# RFDuino_breakout.net
KiCad netlist of a schematic drawn in EAGLE
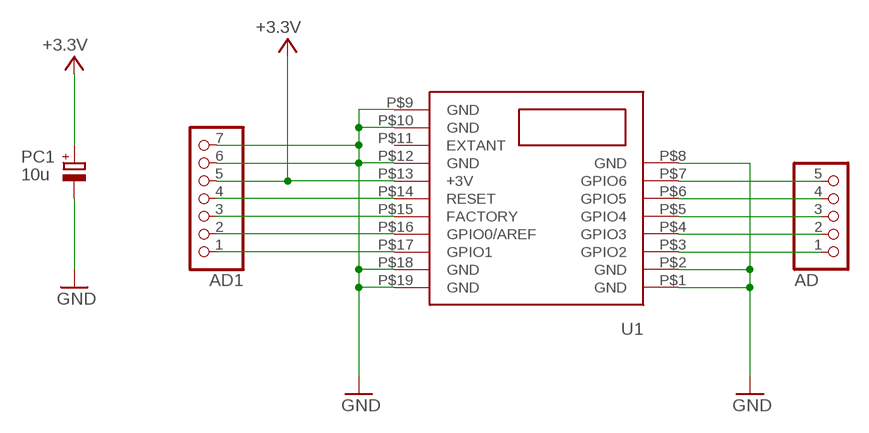
[diagram p0: schematic, sheet 1]

(export (version "E")
  (design (tool "Eeschema 10.0.6"))
  (components
    (comp (ref "AD")
      (value "PINHD-1X5")
      (footprint "eagle-import:1X05")
      (libsource (lib "eagle-import") (part "PINHD-1X5"))
    )
    (comp (ref "AD1")
      (value "PINHD-1X7")
      (footprint "eagle-import:1X07")
      (libsource (lib "eagle-import") (part "PINHD-1X7"))
    )
    (comp (ref "PC1")
      (value "10u")
      (footprint "eagle-import:PANASONIC_D")
      (libsource (lib "eagle-import") (part "CPOL-EUD"))
    )
    (comp (ref "U1")
      (value "RFD22301")
      (footprint "eagle-import:RFD22301")
      (libsource (lib "eagle-import") (part "RFD22301"))
    )
  )
  (nets
    (net (code "1") (name "+3.3V") (class "Default")
      (node (ref "AD1") (pin "5") (pinfunction "5_5") (pintype "passive"))
      (node (ref "PC1") (pin "+") (pinfunction "+_+") (pintype "passive"))
      (node (ref "U1") (pin "P$13") (pinfunction "+3V_P$13") (pintype "bidirectional"))
    )
    (net (code "2") (name "GND") (class "Default")
      (node (ref "AD1") (pin "6") (pinfunction "6_6") (pintype "passive"))
      (node (ref "AD1") (pin "7") (pinfunction "7_7") (pintype "passive"))
      (node (ref "PC1") (pin "-") (pinfunction "-_-") (pintype "passive"))
      (node (ref "U1") (pin "P$1") (pinfunction "GND_P$1") (pintype "bidirectional"))
      (node (ref "U1") (pin "P$10") (pinfunction "GND_P$10") (pintype "bidirectional"))
      (node (ref "U1") (pin "P$12") (pinfunction "GND_P$12") (pintype "bidirectional"))
      (node (ref "U1") (pin "P$18") (pinfunction "GND_P$18") (pintype "bidirectional"))
      (node (ref "U1") (pin "P$19") (pinfunction "GND_P$19") (pintype "bidirectional"))
      (node (ref "U1") (pin "P$2") (pinfunction "GND_P$2") (pintype "bidirectional"))
      (node (ref "U1") (pin "P$8") (pinfunction "GND_P$8") (pintype "bidirectional"))
      (node (ref "U1") (pin "P$9") (pinfunction "GND_P$9") (pintype "bidirectional"))
    )
    (net (code "3") (name "Net-(U1-FACTORY)") (class "Default")
      (node (ref "AD1") (pin "3") (pinfunction "3_3") (pintype "passive"))
      (node (ref "U1") (pin "P$15") (pinfunction "FACTORY_P$15") (pintype "bidirectional"))
    )
    (net (code "4") (name "Net-(U1-GPIO0{slash}AREF)") (class "Default")
      (node (ref "AD1") (pin "2") (pinfunction "2_2") (pintype "passive"))
      (node (ref "U1") (pin "P$16") (pinfunction "GPIO0/AREF_P$16") (pintype "bidirectional"))
    )
    (net (code "5") (name "Net-(U1-GPIO1)") (class "Default")
      (node (ref "AD1") (pin "1") (pinfunction "1_1") (pintype "passive"))
      (node (ref "U1") (pin "P$17") (pinfunction "GPIO1_P$17") (pintype "bidirectional"))
    )
    (net (code "6") (name "Net-(U1-GPIO2)") (class "Default")
      (node (ref "AD") (pin "1") (pinfunction "1_1") (pintype "passive"))
      (node (ref "U1") (pin "P$3") (pinfunction "GPIO2_P$3") (pintype "bidirectional"))
    )
    (net (code "7") (name "Net-(U1-GPIO3)") (class "Default")
      (node (ref "AD") (pin "2") (pinfunction "2_2") (pintype "passive"))
      (node (ref "U1") (pin "P$4") (pinfunction "GPIO3_P$4") (pintype "bidirectional"))
    )
    (net (code "8") (name "Net-(U1-GPIO4)") (class "Default")
      (node (ref "AD") (pin "3") (pinfunction "3_3") (pintype "passive"))
      (node (ref "U1") (pin "P$5") (pinfunction "GPIO4_P$5") (pintype "bidirectional"))
    )
    (net (code "9") (name "Net-(U1-GPIO5)") (class "Default")
      (node (ref "AD") (pin "4") (pinfunction "4_4") (pintype "passive"))
      (node (ref "U1") (pin "P$6") (pinfunction "GPIO5_P$6") (pintype "bidirectional"))
    )
    (net (code "10") (name "Net-(U1-GPIO6)") (class "Default")
      (node (ref "AD") (pin "5") (pinfunction "5_5") (pintype "passive"))
      (node (ref "U1") (pin "P$7") (pinfunction "GPIO6_P$7") (pintype "bidirectional"))
    )
    (net (code "11") (name "Net-(U1-RESET)") (class "Default")
      (node (ref "AD1") (pin "4") (pinfunction "4_4") (pintype "passive"))
      (node (ref "U1") (pin "P$14") (pinfunction "RESET_P$14") (pintype "bidirectional"))
    )
    (net (code "12") (name "unconnected-(U1-EXTANT-PadP$11)") (class "Default")
      (node (ref "U1") (pin "P$11") (pinfunction "EXTANT_P$11") (pintype "bidirectional"))
    )
  )
)
